# Sheet1.net
KiCad netlist of a schematic drawn in Altium Designer
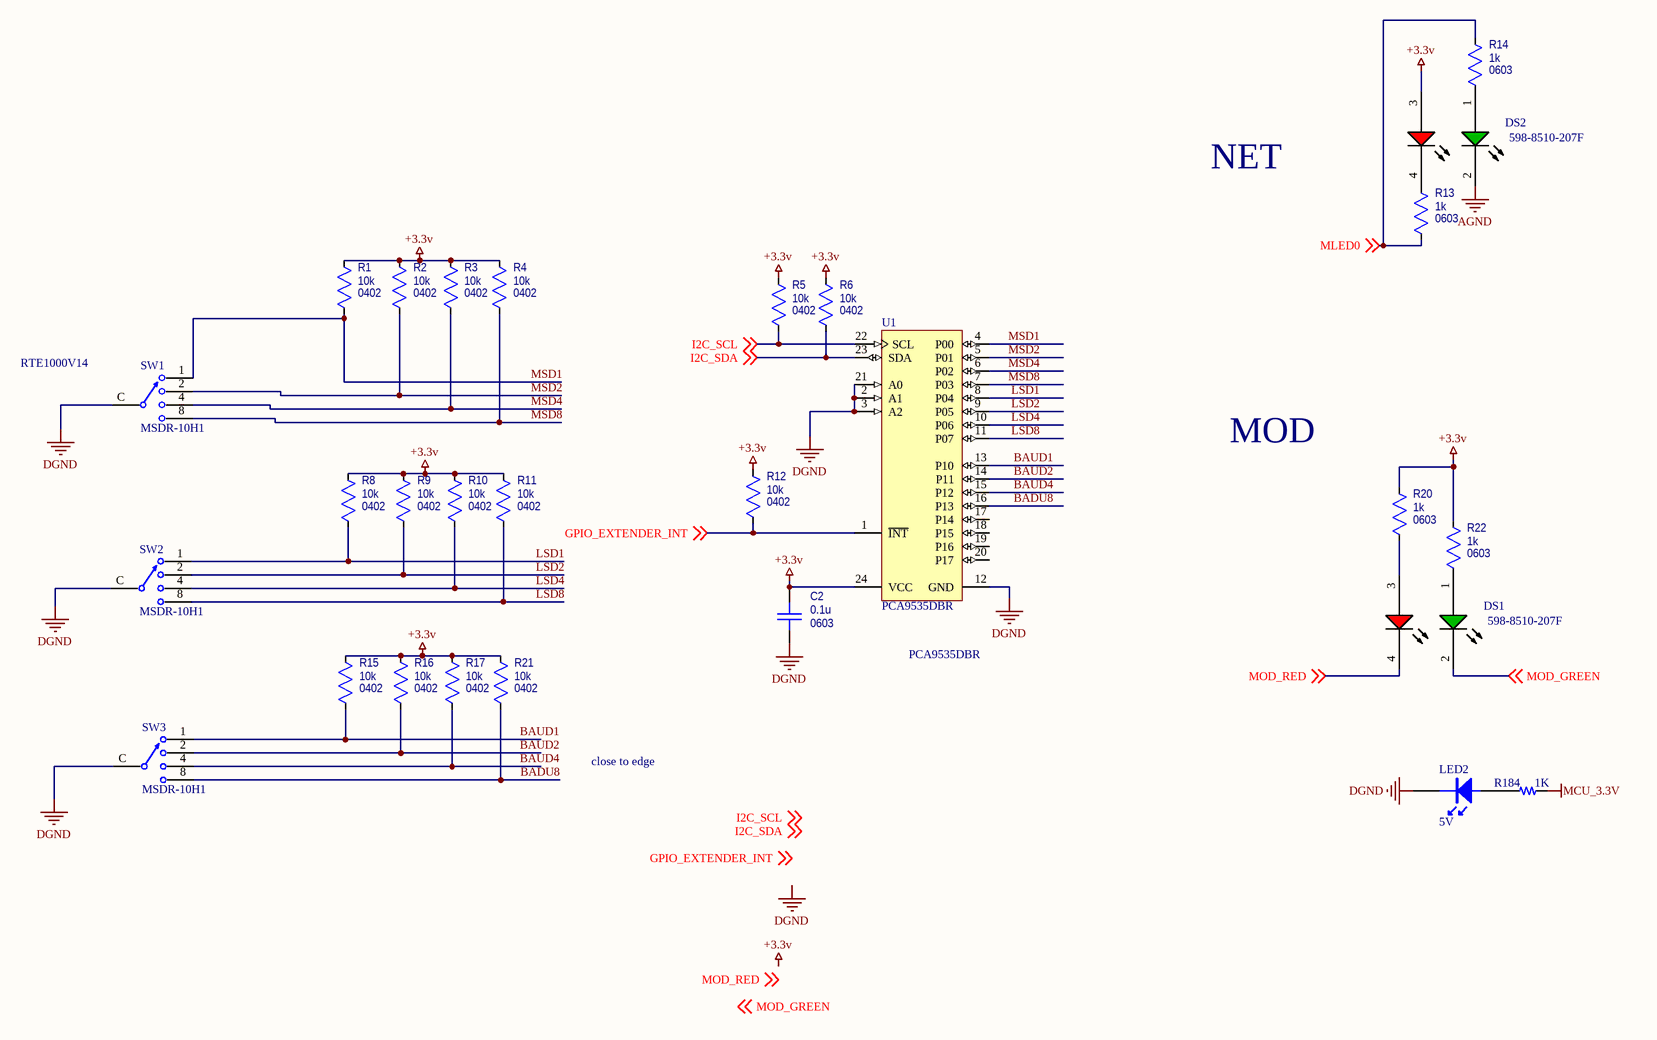
[diagram p0: Sheet1.SchDoc]

(export (version "E")
  (design (tool "Eeschema 10.0.6"))
  (components
    (comp (ref "C2")
      (value "0.1u")
      (footprint "CAPC1608X092N_0603")
      (description "Capacitor, MLCC")
      (fields
        (field (name "MANUFACTURER") "KEMET")
        (field (name "PARTNUMBER") "C0603C104M5RACTU")
        (field (name "PACKAGE") "0603")
      )
      (libsource (lib "Karl") (part "Capacitor_0603"))
    )
    (comp (ref "DS1")
      (value "598-8510-207F")
      (footprint "DIAL-1208-4_V")
      (description "Bi-Color LED, 2.2 V, -40 to 100 degC, 4-Pin SMD (1208), RoHS, Tape and Reel")
      (fields (field (name "MANUFACTURER") "Dialight"))
      (libsource (lib "Bogen") (part "598-8510-207F"))
    )
    (comp (ref "DS2")
      (value "598-8510-207F")
      (footprint "DIAL-1208-4_V")
      (description "Bi-Color LED, 2.2 V, -40 to 100 degC, 4-Pin SMD (1208), RoHS, Tape and Reel")
      (fields (field (name "MANUFACTURER") "Dialight"))
      (libsource (lib "Bogen") (part "598-8510-207F"))
    )
    (comp (ref "LED2") (value "5V") (footprint "0603LED") (libsource (lib "*") (part "LED")))
    (comp (ref "R1")
      (value "10k")
      (footprint "RESC1005X040N_0402")
      (description "Resistor, Standard")
      (fields
        (field (name "MANUFACTURER") "Panasonic")
        (field (name "PARTNUMBER") "ERJ-2RKF1002X")
        (field (name "PACKAGE") "0402")
      )
      (libsource (lib "Karl") (part "Resistor_0402"))
    )
    (comp (ref "R2")
      (value "10k")
      (footprint "RESC1005X040N_0402")
      (description "Resistor, Standard")
      (fields
        (field (name "MANUFACTURER") "Panasonic")
        (field (name "PARTNUMBER") "ERJ-2RKF1002X")
        (field (name "PACKAGE") "0402")
      )
      (libsource (lib "Karl") (part "Resistor_0402"))
    )
    (comp (ref "R3")
      (value "10k")
      (footprint "RESC1005X040N_0402")
      (description "Resistor, Standard")
      (fields
        (field (name "MANUFACTURER") "Panasonic")
        (field (name "PARTNUMBER") "ERJ-2RKF1002X")
        (field (name "PACKAGE") "0402")
      )
      (libsource (lib "Karl") (part "Resistor_0402"))
    )
    (comp (ref "R4")
      (value "10k")
      (footprint "RESC1005X040N_0402")
      (description "Resistor, Standard")
      (fields
        (field (name "MANUFACTURER") "Panasonic")
        (field (name "PARTNUMBER") "ERJ-2RKF1002X")
        (field (name "PACKAGE") "0402")
      )
      (libsource (lib "Karl") (part "Resistor_0402"))
    )
    (comp (ref "R5")
      (value "10k")
      (footprint "RESC1005X040N_0402")
      (description "Resistor, Standard")
      (fields
        (field (name "MANUFACTURER") "Panasonic")
        (field (name "PARTNUMBER") "ERJ-2RKF1002X")
        (field (name "PACKAGE") "0402")
      )
      (libsource (lib "Karl") (part "Resistor_0402"))
    )
    (comp (ref "R6")
      (value "10k")
      (footprint "RESC1005X040N_0402")
      (description "Resistor, Standard")
      (fields
        (field (name "MANUFACTURER") "Panasonic")
        (field (name "PARTNUMBER") "ERJ-2RKF1002X")
        (field (name "PACKAGE") "0402")
      )
      (libsource (lib "Karl") (part "Resistor_0402"))
    )
    (comp (ref "R8")
      (value "10k")
      (footprint "RESC1005X040N_0402")
      (description "Resistor, Standard")
      (fields
        (field (name "MANUFACTURER") "Panasonic")
        (field (name "PARTNUMBER") "ERJ-2RKF1002X")
        (field (name "PACKAGE") "0402")
      )
      (libsource (lib "Karl") (part "Resistor_0402"))
    )
    (comp (ref "R9")
      (value "10k")
      (footprint "RESC1005X040N_0402")
      (description "Resistor, Standard")
      (fields
        (field (name "MANUFACTURER") "Panasonic")
        (field (name "PARTNUMBER") "ERJ-2RKF1002X")
        (field (name "PACKAGE") "0402")
      )
      (libsource (lib "Karl") (part "Resistor_0402"))
    )
    (comp (ref "R10")
      (value "10k")
      (footprint "RESC1005X040N_0402")
      (description "Resistor, Standard")
      (fields
        (field (name "MANUFACTURER") "Panasonic")
        (field (name "PARTNUMBER") "ERJ-2RKF1002X")
        (field (name "PACKAGE") "0402")
      )
      (libsource (lib "Karl") (part "Resistor_0402"))
    )
    (comp (ref "R11")
      (value "10k")
      (footprint "RESC1005X040N_0402")
      (description "Resistor, Standard")
      (fields
        (field (name "MANUFACTURER") "Panasonic")
        (field (name "PARTNUMBER") "ERJ-2RKF1002X")
        (field (name "PACKAGE") "0402")
      )
      (libsource (lib "Karl") (part "Resistor_0402"))
    )
    (comp (ref "R12")
      (value "10k")
      (footprint "RESC1005X040N_0402")
      (description "Resistor, Standard")
      (fields
        (field (name "MANUFACTURER") "Panasonic")
        (field (name "PARTNUMBER") "ERJ-2RKF1002X")
        (field (name "PACKAGE") "0402")
      )
      (libsource (lib "Karl") (part "Resistor_0402"))
    )
    (comp (ref "R13")
      (value "1k")
      (footprint "RESC1608X055N_0603")
      (description "Resistor, Standard")
      (fields
        (field (name "MANUFACTURER") "Yageo")
        (field (name "PARTNUMBER") "RC0603FR-071KL")
        (field (name "PACKAGE") "0603")
      )
      (libsource (lib "Karl") (part "Resistor_0603"))
    )
    (comp (ref "R14")
      (value "1k")
      (footprint "RESC1608X055N_0603")
      (description "Resistor, Standard")
      (fields
        (field (name "MANUFACTURER") "Yageo")
        (field (name "PARTNUMBER") "RC0603FR-071KL")
        (field (name "PACKAGE") "0603")
      )
      (libsource (lib "Karl") (part "Resistor_0603"))
    )
    (comp (ref "R15")
      (value "10k")
      (footprint "RESC1005X040N_0402")
      (description "Resistor, Standard")
      (fields
        (field (name "MANUFACTURER") "Panasonic")
        (field (name "PARTNUMBER") "ERJ-2RKF1002X")
        (field (name "PACKAGE") "0402")
      )
      (libsource (lib "Karl") (part "Resistor_0402"))
    )
    (comp (ref "R16")
      (value "10k")
      (footprint "RESC1005X040N_0402")
      (description "Resistor, Standard")
      (fields
        (field (name "MANUFACTURER") "Panasonic")
        (field (name "PARTNUMBER") "ERJ-2RKF1002X")
        (field (name "PACKAGE") "0402")
      )
      (libsource (lib "Karl") (part "Resistor_0402"))
    )
    (comp (ref "R17")
      (value "10k")
      (footprint "RESC1005X040N_0402")
      (description "Resistor, Standard")
      (fields
        (field (name "MANUFACTURER") "Panasonic")
        (field (name "PARTNUMBER") "ERJ-2RKF1002X")
        (field (name "PACKAGE") "0402")
      )
      (libsource (lib "Karl") (part "Resistor_0402"))
    )
    (comp (ref "R20")
      (value "1k")
      (footprint "RESC1608X055N_0603")
      (description "Resistor, Standard")
      (fields
        (field (name "MANUFACTURER") "Yageo")
        (field (name "PARTNUMBER") "RC0603FR-071KL")
        (field (name "PACKAGE") "0603")
      )
      (libsource (lib "Karl") (part "Resistor_0603"))
    )
    (comp (ref "R21")
      (value "10k")
      (footprint "RESC1005X040N_0402")
      (description "Resistor, Standard")
      (fields
        (field (name "MANUFACTURER") "Panasonic")
        (field (name "PARTNUMBER") "ERJ-2RKF1002X")
        (field (name "PACKAGE") "0402")
      )
      (libsource (lib "Karl") (part "Resistor_0402"))
    )
    (comp (ref "R22")
      (value "1k")
      (footprint "RESC1608X055N_0603")
      (description "Resistor, Standard")
      (fields
        (field (name "MANUFACTURER") "Yageo")
        (field (name "PARTNUMBER") "RC0603FR-071KL")
        (field (name "PACKAGE") "0603")
      )
      (libsource (lib "Karl") (part "Resistor_0603"))
    )
    (comp (ref "R184") (value "1K") (footprint "0603R") (libsource (lib "JRJ_1") (part "R")))
    (comp (ref "SW1")
      (value "MSDR-10H1")
      (footprint "SNGN-MSDR-10H1_V")
      (description "Mini Rotary DIP Switch, 10 Postions, Right Angle Thru-Hole, -60 to 125 degC, 6-Pin THT, RoHS")
      (fields (field (name "PART NO") "MSDR-16H1") (field (name "MANUFACTURER") "SUNGMUN ELECTRONICS"))
      (libsource (lib "Bogen") (part "MSDR-10H1"))
    )
    (comp (ref "SW2")
      (value "MSDR-10H1")
      (footprint "SNGN-MSDR-10H1_V")
      (description "Mini Rotary DIP Switch, 10 Postions, Right Angle Thru-Hole, -60 to 125 degC, 6-Pin THT, RoHS")
      (fields (field (name "PART NO") "MSDR-16H1") (field (name "MANUFACTURER") "SUNGMUN ELECTRONICS"))
      (libsource (lib "Bogen") (part "MSDR-10H1"))
    )
    (comp (ref "SW3")
      (value "MSDR-10H1")
      (footprint "SNGN-MSDR-10H1_V")
      (description "Mini Rotary DIP Switch, 10 Postions, Right Angle Thru-Hole, -60 to 125 degC, 6-Pin THT, RoHS")
      (fields (field (name "PART NO") "MSDR-16H1") (field (name "MANUFACTURER") "SUNGMUN ELECTRONICS"))
      (libsource (lib "Bogen") (part "MSDR-10H1"))
    )
    (comp (ref "U1")
      (value "PCA9535DBR")
      (footprint "DB0024A_L")
      (fields (field (name "MANUFACTURER") "Texas Instruments"))
      (libsource (lib "Bogen") (part "PCA9535DBR"))
    )
  )
  (nets
    (net (code "1") (name "+3.3v") (class "Default")
      (node (ref "C2") (pin "1") (pinfunction "1_1") (pintype "passive"))
      (node (ref "DS2") (pin "3") (pinfunction "RED-A_3") (pintype "passive"))
      (node (ref "R1") (pin "2") (pinfunction "2_2") (pintype "passive"))
      (node (ref "R10") (pin "2") (pinfunction "2_2") (pintype "passive"))
      (node (ref "R11") (pin "2") (pinfunction "2_2") (pintype "passive"))
      (node (ref "R12") (pin "2") (pinfunction "2_2") (pintype "passive"))
      (node (ref "R15") (pin "2") (pinfunction "2_2") (pintype "passive"))
      (node (ref "R16") (pin "2") (pinfunction "2_2") (pintype "passive"))
      (node (ref "R17") (pin "2") (pinfunction "2_2") (pintype "passive"))
      (node (ref "R2") (pin "2") (pinfunction "2_2") (pintype "passive"))
      (node (ref "R20") (pin "2") (pinfunction "2_2") (pintype "passive"))
      (node (ref "R21") (pin "2") (pinfunction "2_2") (pintype "passive"))
      (node (ref "R22") (pin "2") (pinfunction "2_2") (pintype "passive"))
      (node (ref "R3") (pin "2") (pinfunction "2_2") (pintype "passive"))
      (node (ref "R4") (pin "2") (pinfunction "2_2") (pintype "passive"))
      (node (ref "R5") (pin "2") (pinfunction "2_2") (pintype "passive"))
      (node (ref "R6") (pin "2") (pinfunction "2_2") (pintype "passive"))
      (node (ref "R8") (pin "2") (pinfunction "2_2") (pintype "passive"))
      (node (ref "R9") (pin "2") (pinfunction "2_2") (pintype "passive"))
      (node (ref "U1") (pin "24") (pinfunction "VCC_24") (pintype "power_in"))
    )
    (net (code "2") (name "/BADU8") (class "Default")
      (node (ref "R21") (pin "1") (pinfunction "1_1") (pintype "passive"))
      (node (ref "SW3") (pin "8") (pinfunction "8_8") (pintype "passive"))
      (node (ref "U1") (pin "16") (pinfunction "P13_16") (pintype "bidirectional"))
    )
    (net (code "3") (name "/BAUD1") (class "Default")
      (node (ref "R15") (pin "1") (pinfunction "1_1") (pintype "passive"))
      (node (ref "SW3") (pin "1") (pinfunction "1_1") (pintype "passive"))
      (node (ref "U1") (pin "13") (pinfunction "P10_13") (pintype "bidirectional"))
    )
    (net (code "4") (name "/BAUD2") (class "Default")
      (node (ref "R16") (pin "1") (pinfunction "1_1") (pintype "passive"))
      (node (ref "SW3") (pin "2") (pinfunction "2_2") (pintype "passive"))
      (node (ref "U1") (pin "14") (pinfunction "P11_14") (pintype "bidirectional"))
    )
    (net (code "5") (name "/BAUD4") (class "Default")
      (node (ref "R17") (pin "1") (pinfunction "1_1") (pintype "passive"))
      (node (ref "SW3") (pin "4") (pinfunction "4_4") (pintype "passive"))
      (node (ref "U1") (pin "15") (pinfunction "P12_15") (pintype "bidirectional"))
    )
    (net (code "6") (name "/LSD1") (class "Default")
      (node (ref "R8") (pin "1") (pinfunction "1_1") (pintype "passive"))
      (node (ref "SW2") (pin "1") (pinfunction "1_1") (pintype "passive"))
      (node (ref "U1") (pin "8") (pinfunction "P04_8") (pintype "bidirectional"))
    )
    (net (code "7") (name "/LSD2") (class "Default")
      (node (ref "R9") (pin "1") (pinfunction "1_1") (pintype "passive"))
      (node (ref "SW2") (pin "2") (pinfunction "2_2") (pintype "passive"))
      (node (ref "U1") (pin "9") (pinfunction "P05_9") (pintype "bidirectional"))
    )
    (net (code "8") (name "/LSD4") (class "Default")
      (node (ref "R10") (pin "1") (pinfunction "1_1") (pintype "passive"))
      (node (ref "SW2") (pin "4") (pinfunction "4_4") (pintype "passive"))
      (node (ref "U1") (pin "10") (pinfunction "P06_10") (pintype "bidirectional"))
    )
    (net (code "9") (name "/LSD8") (class "Default")
      (node (ref "R11") (pin "1") (pinfunction "1_1") (pintype "passive"))
      (node (ref "SW2") (pin "8") (pinfunction "8_8") (pintype "passive"))
      (node (ref "U1") (pin "11") (pinfunction "P07_11") (pintype "bidirectional"))
    )
    (net (code "10") (name "/MSD1") (class "Default")
      (node (ref "R1") (pin "1") (pinfunction "1_1") (pintype "passive"))
      (node (ref "SW1") (pin "1") (pinfunction "1_1") (pintype "passive"))
      (node (ref "U1") (pin "4") (pinfunction "P00_4") (pintype "bidirectional"))
    )
    (net (code "11") (name "/MSD2") (class "Default")
      (node (ref "R2") (pin "1") (pinfunction "1_1") (pintype "passive"))
      (node (ref "SW1") (pin "2") (pinfunction "2_2") (pintype "passive"))
      (node (ref "U1") (pin "5") (pinfunction "P01_5") (pintype "bidirectional"))
    )
    (net (code "12") (name "/MSD4") (class "Default")
      (node (ref "R3") (pin "1") (pinfunction "1_1") (pintype "passive"))
      (node (ref "SW1") (pin "4") (pinfunction "4_4") (pintype "passive"))
      (node (ref "U1") (pin "6") (pinfunction "P02_6") (pintype "bidirectional"))
    )
    (net (code "13") (name "/MSD8") (class "Default")
      (node (ref "R4") (pin "1") (pinfunction "1_1") (pintype "passive"))
      (node (ref "SW1") (pin "8") (pinfunction "8_8") (pintype "passive"))
      (node (ref "U1") (pin "7") (pinfunction "P03_7") (pintype "bidirectional"))
    )
    (net (code "14") (name "AGND") (class "Default")
      (node (ref "DS2") (pin "2") (pinfunction "GREEN-K_2") (pintype "passive"))
    )
    (net (code "15") (name "DGND") (class "Default")
      (node (ref "C2") (pin "2") (pinfunction "2_2") (pintype "passive"))
      (node (ref "LED2") (pin "2") (pinfunction "2_2") (pintype "passive"))
      (node (ref "SW1") (pin "C") (pinfunction "C_C") (pintype "passive"))
      (node (ref "SW2") (pin "C") (pinfunction "C_C") (pintype "passive"))
      (node (ref "SW3") (pin "C") (pinfunction "C_C") (pintype "passive"))
      (node (ref "U1") (pin "12") (pinfunction "GND_12") (pintype "power_in"))
      (node (ref "U1") (pin "2") (pinfunction "A1_2") (pintype "input"))
      (node (ref "U1") (pin "21") (pinfunction "A0_21") (pintype "input"))
      (node (ref "U1") (pin "3") (pinfunction "A2_3") (pintype "input"))
    )
    (net (code "16") (name "GPIO_EXTENDER_INT") (class "Default")
      (node (ref "R12") (pin "1") (pinfunction "1_1") (pintype "passive"))
      (node (ref "U1") (pin "1") (pinfunction "~{INT}_1") (pintype "open_collector"))
    )
    (net (code "17") (name "I2C_SCL") (class "Default")
      (node (ref "R5") (pin "1") (pinfunction "1_1") (pintype "passive"))
      (node (ref "U1") (pin "22") (pinfunction "SCL_22") (pintype "input"))
    )
    (net (code "18") (name "I2C_SDA") (class "Default")
      (node (ref "R6") (pin "1") (pinfunction "1_1") (pintype "passive"))
      (node (ref "U1") (pin "23") (pinfunction "SDA_23") (pintype "bidirectional"))
    )
    (net (code "19") (name "MCU_3.3V") (class "Default") (node (ref "R184") (pin "2") (pintype "passive")))
    (net (code "20") (name "MLED0") (class "Default")
      (node (ref "R13") (pin "1") (pinfunction "1_1") (pintype "passive"))
      (node (ref "R14") (pin "2") (pinfunction "2_2") (pintype "passive"))
    )
    (net (code "21") (name "MOD_GREEN") (class "Default")
      (node (ref "DS1") (pin "2") (pinfunction "GREEN-K_2") (pintype "passive"))
    )
    (net (code "22") (name "MOD_RED") (class "Default")
      (node (ref "DS1") (pin "4") (pinfunction "RED-K_4") (pintype "passive"))
    )
    (net (code "23") (name "Net-(DS1-GREEN-A)") (class "Default")
      (node (ref "DS1") (pin "1") (pinfunction "GREEN-A_1") (pintype "passive"))
      (node (ref "R22") (pin "1") (pinfunction "1_1") (pintype "passive"))
    )
    (net (code "24") (name "Net-(DS1-RED-A)") (class "Default")
      (node (ref "DS1") (pin "3") (pinfunction "RED-A_3") (pintype "passive"))
      (node (ref "R20") (pin "1") (pinfunction "1_1") (pintype "passive"))
    )
    (net (code "25") (name "Net-(DS2-GREEN-A)") (class "Default")
      (node (ref "DS2") (pin "1") (pinfunction "GREEN-A_1") (pintype "passive"))
      (node (ref "R14") (pin "1") (pinfunction "1_1") (pintype "passive"))
    )
    (net (code "26") (name "Net-(DS2-RED-K)") (class "Default")
      (node (ref "DS2") (pin "4") (pinfunction "RED-K_4") (pintype "passive"))
      (node (ref "R13") (pin "2") (pinfunction "2_2") (pintype "passive"))
    )
    (net (code "27") (name "Net-(LED2-Pad1)") (class "Default")
      (node (ref "LED2") (pin "1") (pinfunction "1_1") (pintype "passive"))
      (node (ref "R184") (pin "1") (pintype "passive"))
    )
    (net (code "28") (name "unconnected-(U1-P14-Pad17)") (class "Default")
      (node (ref "U1") (pin "17") (pinfunction "P14_17") (pintype "bidirectional"))
    )
    (net (code "29") (name "unconnected-(U1-P15-Pad18)") (class "Default")
      (node (ref "U1") (pin "18") (pinfunction "P15_18") (pintype "bidirectional"))
    )
    (net (code "30") (name "unconnected-(U1-P16-Pad19)") (class "Default")
      (node (ref "U1") (pin "19") (pinfunction "P16_19") (pintype "bidirectional"))
    )
    (net (code "31") (name "unconnected-(U1-P17-Pad20)") (class "Default")
      (node (ref "U1") (pin "20") (pinfunction "P17_20") (pintype "bidirectional"))
    )
  )
)
